# MRCS-Enhanced-Optical-Position-Detector.net
KiCad netlist of a schematic drawn in EAGLE
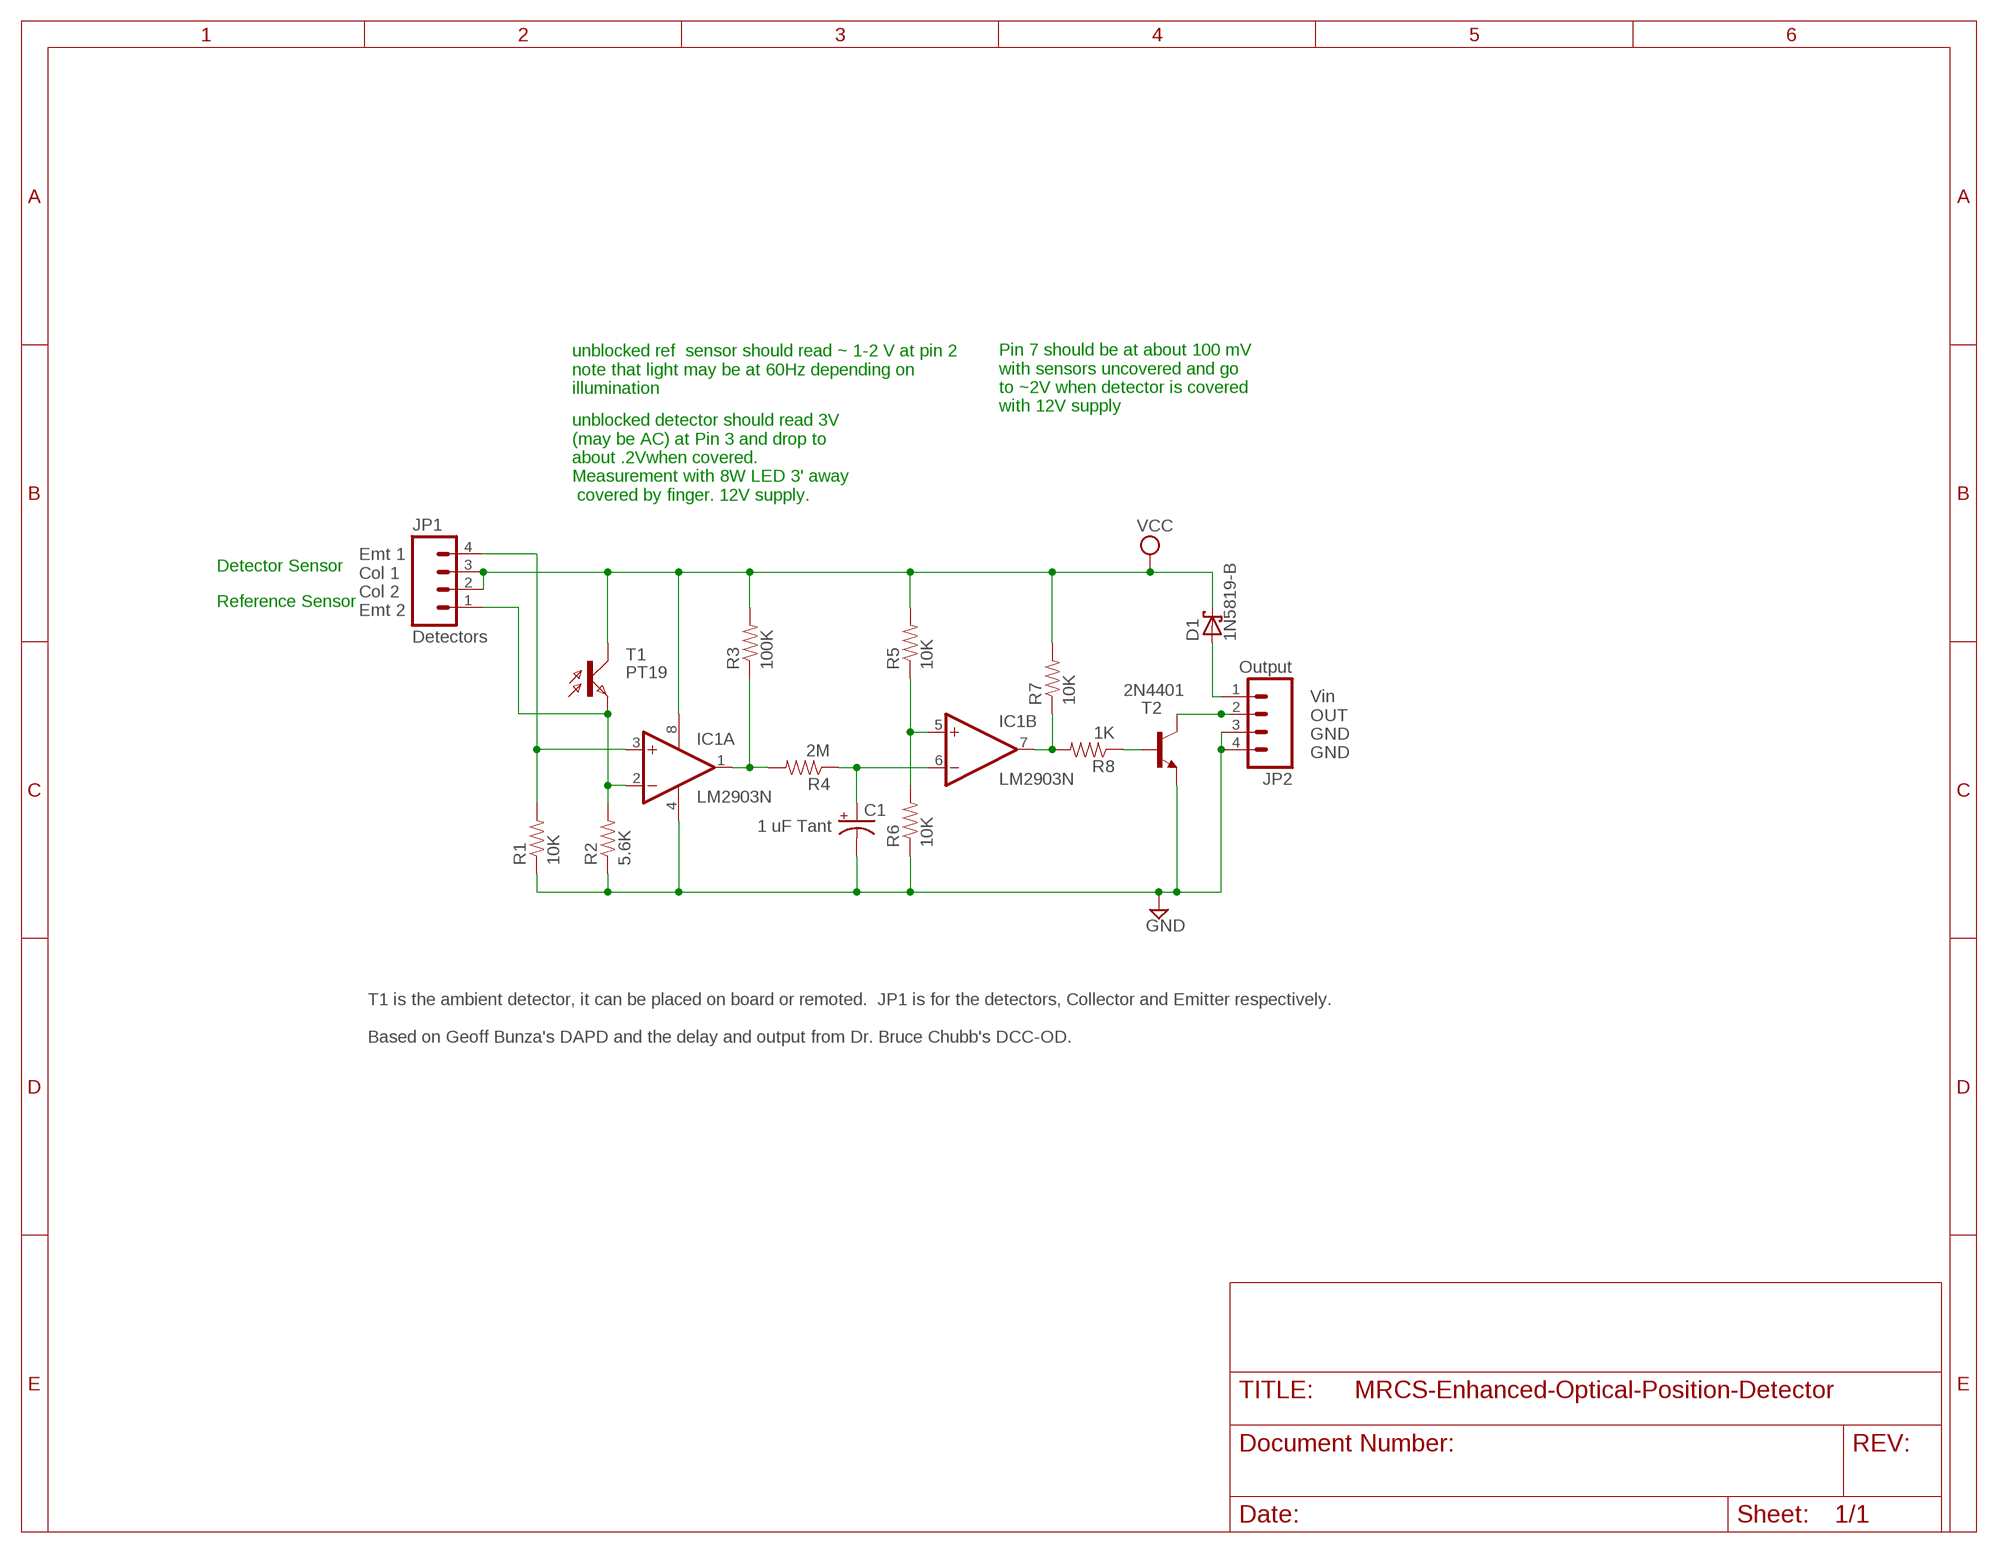
[diagram p0: schematic, sheet 1]

(export (version "E")
  (design (tool "Eeschema 10.0.6"))
  (components
    (comp (ref "C1")
      (value "1 uF Tant")
      (footprint "eagle-import:E2,5-5")
      (libsource (lib "eagle-import") (part "CPOL-USE2.5-5"))
    )
    (comp (ref "D1")
      (value "1N5819-B")
      (footprint "eagle-import:DO41-7.6")
      (libsource (lib "eagle-import") (part "1N5819-B"))
    )
    (comp (ref "IC1")
      (value "LM2903N")
      (footprint "eagle-import:DIL08")
      (libsource (lib "eagle-import") (part "LM2903N"))
    )
    (comp (ref "JP1")
      (value "Detectors")
      (footprint "eagle-import:1X04_LOCK")
      (libsource (lib "eagle-import") (part "M04LOCK"))
    )
    (comp (ref "JP2")
      (value "Output")
      (footprint "eagle-import:1X04_LOCK")
      (libsource (lib "eagle-import") (part "M04LOCK"))
    )
    (comp (ref "R1")
      (value "10K")
      (footprint "eagle-import:AXIAL-0.4")
      (libsource (lib "eagle-import") (part "RESISTORPTH-1/4W"))
    )
    (comp (ref "R2")
      (value "5.6K")
      (footprint "eagle-import:AXIAL-0.4")
      (libsource (lib "eagle-import") (part "RESISTORPTH-1/4W"))
    )
    (comp (ref "R3")
      (value "100K")
      (footprint "eagle-import:AXIAL-0.4")
      (libsource (lib "eagle-import") (part "RESISTORPTH-1/4W"))
    )
    (comp (ref "R4")
      (value "2M")
      (footprint "eagle-import:AXIAL-0.4")
      (libsource (lib "eagle-import") (part "RESISTORPTH-1/4W"))
    )
    (comp (ref "R5")
      (value "10K")
      (footprint "eagle-import:AXIAL-0.4")
      (libsource (lib "eagle-import") (part "RESISTORPTH-1/4W"))
    )
    (comp (ref "R6")
      (value "10K")
      (footprint "eagle-import:AXIAL-0.4")
      (libsource (lib "eagle-import") (part "RESISTORPTH-1/4W"))
    )
    (comp (ref "R7")
      (value "10K")
      (footprint "eagle-import:AXIAL-0.4")
      (libsource (lib "eagle-import") (part "RESISTORPTH-1/4W"))
    )
    (comp (ref "R8")
      (value "1K")
      (footprint "eagle-import:AXIAL-0.4")
      (libsource (lib "eagle-import") (part "RESISTORPTH-1/4W"))
    )
    (comp (ref "T1")
      (value "PT19")
      (footprint "eagle-import:BPX81")
      (libsource (lib "eagle-import") (part "BPX81"))
    )
    (comp (ref "T2")
      (value "2N4401")
      (footprint "eagle-import:TO92-EBC")
      (libsource (lib "eagle-import") (part "-NPN-TO92-EBC2N3904"))
    )
  )
  (nets
    (net (code "1") (name "GND") (class "Default")
      (node (ref "C1") (pin "-") (pinfunction "-_-") (pintype "passive"))
      (node (ref "IC1") (pin "4") (pinfunction "V-_4") (pintype "power_in"))
      (node (ref "JP2") (pin "3") (pinfunction "3_3") (pintype "passive"))
      (node (ref "JP2") (pin "4") (pinfunction "4_4") (pintype "passive"))
      (node (ref "R1") (pin "P$1") (pinfunction "1_P$1") (pintype "passive"))
      (node (ref "R2") (pin "P$1") (pinfunction "1_P$1") (pintype "passive"))
      (node (ref "R6") (pin "P$1") (pinfunction "1_P$1") (pintype "passive"))
      (node (ref "T2") (pin "E") (pinfunction "E_E") (pintype "passive"))
    )
    (net (code "2") (name "Net-(D1-PadA)") (class "Default")
      (node (ref "D1") (pin "A") (pinfunction "A_A") (pintype "passive"))
      (node (ref "JP2") (pin "1") (pinfunction "1_1") (pintype "passive"))
    )
    (net (code "3") (name "Net-(IC1A-+IN)") (class "Default")
      (node (ref "IC1") (pin "3") (pinfunction "+IN_3") (pintype "input"))
      (node (ref "JP1") (pin "4") (pinfunction "4_4") (pintype "passive"))
      (node (ref "R1") (pin "P$2") (pinfunction "2_P$2") (pintype "passive"))
    )
    (net (code "4") (name "Net-(IC1A--IN)") (class "Default")
      (node (ref "IC1") (pin "2") (pinfunction "-IN_2") (pintype "input"))
      (node (ref "JP1") (pin "1") (pinfunction "1_1") (pintype "passive"))
      (node (ref "R2") (pin "P$2") (pinfunction "2_P$2") (pintype "passive"))
      (node (ref "T1") (pin "E") (pinfunction "E_E") (pintype "passive"))
    )
    (net (code "5") (name "Net-(IC1A-OUT)") (class "Default")
      (node (ref "IC1") (pin "1") (pinfunction "OUT_1") (pintype "output"))
      (node (ref "R3") (pin "P$1") (pinfunction "1_P$1") (pintype "passive"))
      (node (ref "R4") (pin "P$2") (pinfunction "2_P$2") (pintype "passive"))
    )
    (net (code "6") (name "Net-(IC1B-+IN)") (class "Default")
      (node (ref "IC1") (pin "5") (pinfunction "+IN_5") (pintype "input"))
      (node (ref "R5") (pin "P$1") (pinfunction "1_P$1") (pintype "passive"))
      (node (ref "R6") (pin "P$2") (pinfunction "2_P$2") (pintype "passive"))
    )
    (net (code "7") (name "Net-(IC1B--IN)") (class "Default")
      (node (ref "C1") (pin "+") (pinfunction "+_+") (pintype "passive"))
      (node (ref "IC1") (pin "6") (pinfunction "-IN_6") (pintype "input"))
      (node (ref "R4") (pin "P$1") (pinfunction "1_P$1") (pintype "passive"))
    )
    (net (code "8") (name "Net-(IC1B-OUT)") (class "Default")
      (node (ref "IC1") (pin "7") (pinfunction "OUT_7") (pintype "output"))
      (node (ref "R7") (pin "P$1") (pinfunction "1_P$1") (pintype "passive"))
      (node (ref "R8") (pin "P$2") (pinfunction "2_P$2") (pintype "passive"))
    )
    (net (code "9") (name "Net-(JP2-Pad2)") (class "Default")
      (node (ref "JP2") (pin "2") (pinfunction "2_2") (pintype "passive"))
      (node (ref "T2") (pin "C") (pinfunction "C_C") (pintype "passive"))
    )
    (net (code "10") (name "Net-(R8-1)") (class "Default")
      (node (ref "R8") (pin "P$1") (pinfunction "1_P$1") (pintype "passive"))
      (node (ref "T2") (pin "B") (pinfunction "B_B") (pintype "passive"))
    )
    (net (code "11") (name "VCC") (class "Default")
      (node (ref "D1") (pin "C") (pinfunction "C_C") (pintype "passive"))
      (node (ref "IC1") (pin "8") (pinfunction "V+_8") (pintype "power_in"))
      (node (ref "JP1") (pin "2") (pinfunction "2_2") (pintype "passive"))
      (node (ref "JP1") (pin "3") (pinfunction "3_3") (pintype "passive"))
      (node (ref "R3") (pin "P$2") (pinfunction "2_P$2") (pintype "passive"))
      (node (ref "R5") (pin "P$2") (pinfunction "2_P$2") (pintype "passive"))
      (node (ref "R7") (pin "P$2") (pinfunction "2_P$2") (pintype "passive"))
      (node (ref "T1") (pin "C") (pinfunction "C_C") (pintype "passive"))
    )
  )
)
